# r1_ar_0_1b.net
KiCad netlist of a schematic drawn in EAGLE
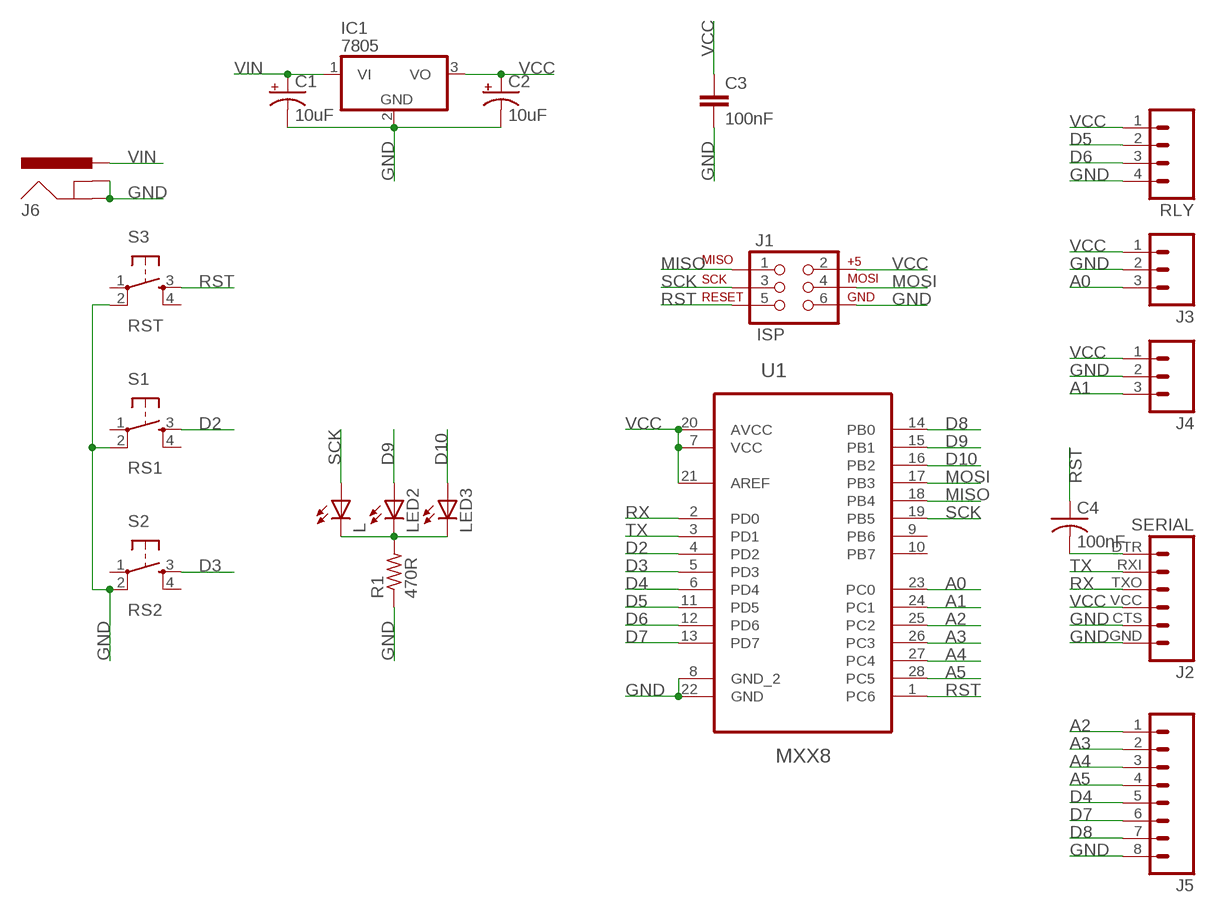
[diagram p0: schematic, sheet 1]

(export (version "E")
  (design (tool "Eeschema 10.0.6"))
  (components
    (comp (ref "C1")
      (value "10uF")
      (footprint "eagle-import:153CLV-0405")
      (libsource (lib "eagle-import") (part "CPOL-US153CLV-0405"))
    )
    (comp (ref "C2")
      (value "10uF")
      (footprint "eagle-import:153CLV-0405")
      (libsource (lib "eagle-import") (part "CPOL-US153CLV-0405"))
    )
    (comp (ref "C3")
      (value "100nF")
      (footprint "eagle-import:CAP-PTH-SMALL")
      (libsource (lib "eagle-import") (part "CAPPTH"))
    )
    (comp (ref "C4")
      (value "100nF")
      (footprint "eagle-import:C1206K")
      (libsource (lib "eagle-import") (part "C-USC1206K"))
    )
    (comp (ref "IC1")
      (value "7805")
      (footprint "eagle-import:TO220V")
      (libsource (lib "eagle-import") (part "78TV05"))
    )
    (comp (ref "J1")
      (value "ISP")
      (footprint "eagle-import:2X3_LOCK")
      (libsource (lib "eagle-import") (part "AVR_SPI_PRG_62X3_LOCK"))
    )
    (comp (ref "J2")
      (value "SERIAL")
      (footprint "eagle-import:FTDI_BASIC")
      (libsource (lib "eagle-import") (part "FTDI_BASICPTH"))
    )
    (comp (ref "J3")
      (value "M03PTH")
      (footprint "eagle-import:1X03")
      (libsource (lib "eagle-import") (part "M03PTH"))
    )
    (comp (ref "J4")
      (value "M03PTH")
      (footprint "eagle-import:1X03")
      (libsource (lib "eagle-import") (part "M03PTH"))
    )
    (comp (ref "J5")
      (value "M08SILK_FEMALE_PTH")
      (footprint "eagle-import:1X08")
      (libsource (lib "eagle-import") (part "M08SILK_FEMALE_PTH"))
    )
    (comp (ref "J6")
      (value "POWER_JACKSLT")
      (footprint "eagle-import:POWER_JACK_SLOT")
      (libsource (lib "eagle-import") (part "POWER_JACKSLT"))
    )
    (comp (ref "L")
      (value "LEDSML0805")
      (footprint "eagle-import:SML0805")
      (libsource (lib "eagle-import") (part "LEDSML0805"))
    )
    (comp (ref "LED2")
      (value "LEDSML0805")
      (footprint "eagle-import:SML0805")
      (libsource (lib "eagle-import") (part "LEDSML0805"))
    )
    (comp (ref "LED3")
      (value "LEDSML0805")
      (footprint "eagle-import:SML0805")
      (libsource (lib "eagle-import") (part "LEDSML0805"))
    )
    (comp (ref "R1")
      (value "470R")
      (footprint "eagle-import:M0805")
      (libsource (lib "eagle-import") (part "R-US_M0805"))
    )
    (comp (ref "RLY")
      (value "M04PTH")
      (footprint "eagle-import:1X04")
      (libsource (lib "eagle-import") (part "M04PTH"))
    )
    (comp (ref "S1")
      (value "RS1")
      (footprint "eagle-import:TACTILE-SWITCH-SMD")
      (libsource (lib "eagle-import") (part "TAC_SWITCHSMD"))
    )
    (comp (ref "S2")
      (value "RS2")
      (footprint "eagle-import:TACTILE-SWITCH-SMD")
      (libsource (lib "eagle-import") (part "TAC_SWITCHSMD"))
    )
    (comp (ref "S3")
      (value "RST")
      (footprint "eagle-import:TACTILE-SWITCH-SMD")
      (libsource (lib "eagle-import") (part "TAC_SWITCHSMD"))
    )
    (comp (ref "U1")
      (value "MXX8")
      (footprint "eagle-import:DIP254P762X457-28")
      (fields (field (name "MPN") "ATMEGA88A-PU"))
      (libsource (lib "eagle-import") (part "ATMEGA88A-PU"))
    )
  )
  (nets
    (net (code "1") (name "/A0") (class "Default")
      (node (ref "J3") (pin "3") (pinfunction "3_3") (pintype "passive"))
      (node (ref "U1") (pin "23") (pinfunction "PC0_23") (pintype "bidirectional"))
    )
    (net (code "2") (name "/A1") (class "Default")
      (node (ref "J4") (pin "3") (pinfunction "3_3") (pintype "passive"))
      (node (ref "U1") (pin "24") (pinfunction "PC1_24") (pintype "bidirectional"))
    )
    (net (code "3") (name "/A2") (class "Default")
      (node (ref "J5") (pin "1") (pinfunction "1_1") (pintype "passive"))
      (node (ref "U1") (pin "25") (pinfunction "PC2_25") (pintype "bidirectional"))
    )
    (net (code "4") (name "/A3") (class "Default")
      (node (ref "J5") (pin "2") (pinfunction "2_2") (pintype "passive"))
      (node (ref "U1") (pin "26") (pinfunction "PC3_26") (pintype "bidirectional"))
    )
    (net (code "5") (name "/A4") (class "Default")
      (node (ref "J5") (pin "3") (pinfunction "3_3") (pintype "passive"))
      (node (ref "U1") (pin "27") (pinfunction "PC4_27") (pintype "bidirectional"))
    )
    (net (code "6") (name "/A5") (class "Default")
      (node (ref "J5") (pin "4") (pinfunction "4_4") (pintype "passive"))
      (node (ref "U1") (pin "28") (pinfunction "PC5_28") (pintype "bidirectional"))
    )
    (net (code "7") (name "/D2") (class "Default")
      (node (ref "S1") (pin "3") (pinfunction "3_3") (pintype "passive"))
      (node (ref "U1") (pin "4") (pinfunction "PD2_4") (pintype "bidirectional"))
    )
    (net (code "8") (name "/D3") (class "Default")
      (node (ref "S2") (pin "3") (pinfunction "3_3") (pintype "passive"))
      (node (ref "U1") (pin "5") (pinfunction "PD3_5") (pintype "bidirectional"))
    )
    (net (code "9") (name "/D4") (class "Default")
      (node (ref "J5") (pin "5") (pinfunction "5_5") (pintype "passive"))
      (node (ref "U1") (pin "6") (pinfunction "PD4_6") (pintype "bidirectional"))
    )
    (net (code "10") (name "/D5") (class "Default")
      (node (ref "RLY") (pin "2") (pinfunction "2_2") (pintype "passive"))
      (node (ref "U1") (pin "11") (pinfunction "PD5_11") (pintype "bidirectional"))
    )
    (net (code "11") (name "/D6") (class "Default")
      (node (ref "RLY") (pin "3") (pinfunction "3_3") (pintype "passive"))
      (node (ref "U1") (pin "12") (pinfunction "PD6_12") (pintype "bidirectional"))
    )
    (net (code "12") (name "/D7") (class "Default")
      (node (ref "J5") (pin "6") (pinfunction "6_6") (pintype "passive"))
      (node (ref "U1") (pin "13") (pinfunction "PD7_13") (pintype "bidirectional"))
    )
    (net (code "13") (name "/D8") (class "Default")
      (node (ref "J5") (pin "7") (pinfunction "7_7") (pintype "passive"))
      (node (ref "U1") (pin "14") (pinfunction "PB0_14") (pintype "bidirectional"))
    )
    (net (code "14") (name "/D9") (class "Default")
      (node (ref "LED2") (pin "A") (pinfunction "A_A") (pintype "passive"))
      (node (ref "U1") (pin "15") (pinfunction "PB1_15") (pintype "bidirectional"))
    )
    (net (code "15") (name "/D10") (class "Default")
      (node (ref "LED3") (pin "A") (pinfunction "A_A") (pintype "passive"))
      (node (ref "U1") (pin "16") (pinfunction "PB2_16") (pintype "bidirectional"))
    )
    (net (code "16") (name "/GND") (class "Default")
      (node (ref "C1") (pin "-") (pinfunction "-_-") (pintype "passive"))
      (node (ref "C2") (pin "-") (pinfunction "-_-") (pintype "passive"))
      (node (ref "C3") (pin "2") (pinfunction "2_2") (pintype "passive"))
      (node (ref "IC1") (pin "2") (pinfunction "GND_2") (pintype "passive"))
      (node (ref "J1") (pin "6") (pinfunction "6_6") (pintype "passive"))
      (node (ref "J2") (pin "CTS") (pinfunction "5_CTS") (pintype "passive"))
      (node (ref "J2") (pin "GND") (pinfunction "6_GND") (pintype "passive"))
      (node (ref "J3") (pin "2") (pinfunction "2_2") (pintype "passive"))
      (node (ref "J4") (pin "2") (pinfunction "2_2") (pintype "passive"))
      (node (ref "J5") (pin "8") (pinfunction "8_8") (pintype "passive"))
      (node (ref "J6") (pin "GND@1") (pinfunction "GNDBREAK_GND@1") (pintype "bidirectional"))
      (node (ref "J6") (pin "GND@2") (pinfunction "GND_GND@2") (pintype "bidirectional"))
      (node (ref "R1") (pin "1") (pinfunction "1_1") (pintype "passive"))
      (node (ref "RLY") (pin "4") (pinfunction "4_4") (pintype "passive"))
      (node (ref "S1") (pin "2") (pinfunction "2_2") (pintype "passive"))
      (node (ref "S2") (pin "2") (pinfunction "2_2") (pintype "passive"))
      (node (ref "S3") (pin "2") (pinfunction "2_2") (pintype "passive"))
      (node (ref "U1") (pin "22") (pinfunction "GND_22") (pintype "passive"))
      (node (ref "U1") (pin "8") (pinfunction "GND_2_8") (pintype "passive"))
    )
    (net (code "17") (name "/MISO") (class "Default")
      (node (ref "J1") (pin "1") (pinfunction "1_1") (pintype "passive"))
      (node (ref "U1") (pin "18") (pinfunction "PB4_18") (pintype "bidirectional"))
    )
    (net (code "18") (name "/MOSI") (class "Default")
      (node (ref "J1") (pin "4") (pinfunction "4_4") (pintype "passive"))
      (node (ref "U1") (pin "17") (pinfunction "PB3_17") (pintype "bidirectional"))
    )
    (net (code "19") (name "/RST") (class "Default")
      (node (ref "C4") (pin "1") (pinfunction "1_1") (pintype "passive"))
      (node (ref "J1") (pin "5") (pinfunction "5_5") (pintype "passive"))
      (node (ref "S3") (pin "3") (pinfunction "3_3") (pintype "passive"))
      (node (ref "U1") (pin "1") (pinfunction "PC6_1") (pintype "bidirectional"))
    )
    (net (code "20") (name "/RX") (class "Default")
      (node (ref "J2") (pin "TXO") (pinfunction "3_TXO") (pintype "passive"))
      (node (ref "U1") (pin "2") (pinfunction "PD0_2") (pintype "bidirectional"))
    )
    (net (code "21") (name "/SCK") (class "Default")
      (node (ref "J1") (pin "3") (pinfunction "3_3") (pintype "passive"))
      (node (ref "L") (pin "A") (pinfunction "A_A") (pintype "passive"))
      (node (ref "U1") (pin "19") (pinfunction "PB5_19") (pintype "bidirectional"))
    )
    (net (code "22") (name "/TX") (class "Default")
      (node (ref "J2") (pin "RXI") (pinfunction "2_RXI") (pintype "passive"))
      (node (ref "U1") (pin "3") (pinfunction "PD1_3") (pintype "bidirectional"))
    )
    (net (code "23") (name "/VCC") (class "Default")
      (node (ref "C2") (pin "+") (pinfunction "+_+") (pintype "passive"))
      (node (ref "C3") (pin "1") (pinfunction "1_1") (pintype "passive"))
      (node (ref "IC1") (pin "3") (pinfunction "VO_3") (pintype "passive"))
      (node (ref "J1") (pin "2") (pinfunction "2_2") (pintype "passive"))
      (node (ref "J2") (pin "VCC") (pinfunction "4_VCC") (pintype "passive"))
      (node (ref "J3") (pin "1") (pinfunction "1_1") (pintype "passive"))
      (node (ref "J4") (pin "1") (pinfunction "1_1") (pintype "passive"))
      (node (ref "RLY") (pin "1") (pinfunction "1_1") (pintype "passive"))
      (node (ref "U1") (pin "20") (pinfunction "AVCC_20") (pintype "power_in"))
      (node (ref "U1") (pin "21") (pinfunction "AREF_21") (pintype "input"))
      (node (ref "U1") (pin "7") (pinfunction "VCC_7") (pintype "power_in"))
    )
    (net (code "24") (name "/VIN") (class "Default")
      (node (ref "C1") (pin "+") (pinfunction "+_+") (pintype "passive"))
      (node (ref "IC1") (pin "1") (pinfunction "VI_1") (pintype "input"))
      (node (ref "J6") (pin "PWR") (pinfunction "PWR_PWR") (pintype "bidirectional"))
    )
    (net (code "25") (name "Net-(J2-1)") (class "Default")
      (node (ref "C4") (pin "2") (pinfunction "2_2") (pintype "passive"))
      (node (ref "J2") (pin "DTR") (pinfunction "1_DTR") (pintype "passive"))
    )
    (net (code "26") (name "Net-(L-PadC)") (class "Default")
      (node (ref "L") (pin "C") (pinfunction "C_C") (pintype "passive"))
      (node (ref "LED2") (pin "C") (pinfunction "C_C") (pintype "passive"))
      (node (ref "LED3") (pin "C") (pinfunction "C_C") (pintype "passive"))
      (node (ref "R1") (pin "2") (pinfunction "2_2") (pintype "passive"))
    )
    (net (code "27") (name "unconnected-(S1-Pad1)") (class "Default")
      (node (ref "S1") (pin "1") (pinfunction "1_1") (pintype "passive"))
    )
    (net (code "28") (name "unconnected-(S1-Pad4)") (class "Default")
      (node (ref "S1") (pin "4") (pinfunction "4_4") (pintype "passive"))
    )
    (net (code "29") (name "unconnected-(S2-Pad1)") (class "Default")
      (node (ref "S2") (pin "1") (pinfunction "1_1") (pintype "passive"))
    )
    (net (code "30") (name "unconnected-(S2-Pad4)") (class "Default")
      (node (ref "S2") (pin "4") (pinfunction "4_4") (pintype "passive"))
    )
    (net (code "31") (name "unconnected-(S3-Pad1)") (class "Default")
      (node (ref "S3") (pin "1") (pinfunction "1_1") (pintype "passive"))
    )
    (net (code "32") (name "unconnected-(S3-Pad4)") (class "Default")
      (node (ref "S3") (pin "4") (pinfunction "4_4") (pintype "passive"))
    )
    (net (code "33") (name "unconnected-(U1-PB6-Pad9)") (class "Default")
      (node (ref "U1") (pin "9") (pinfunction "PB6_9") (pintype "bidirectional"))
    )
    (net (code "34") (name "unconnected-(U1-PB7-Pad10)") (class "Default")
      (node (ref "U1") (pin "10") (pinfunction "PB7_10") (pintype "bidirectional"))
    )
  )
)
